# Sheet1.net
KiCad netlist of a schematic drawn in Altium Designer
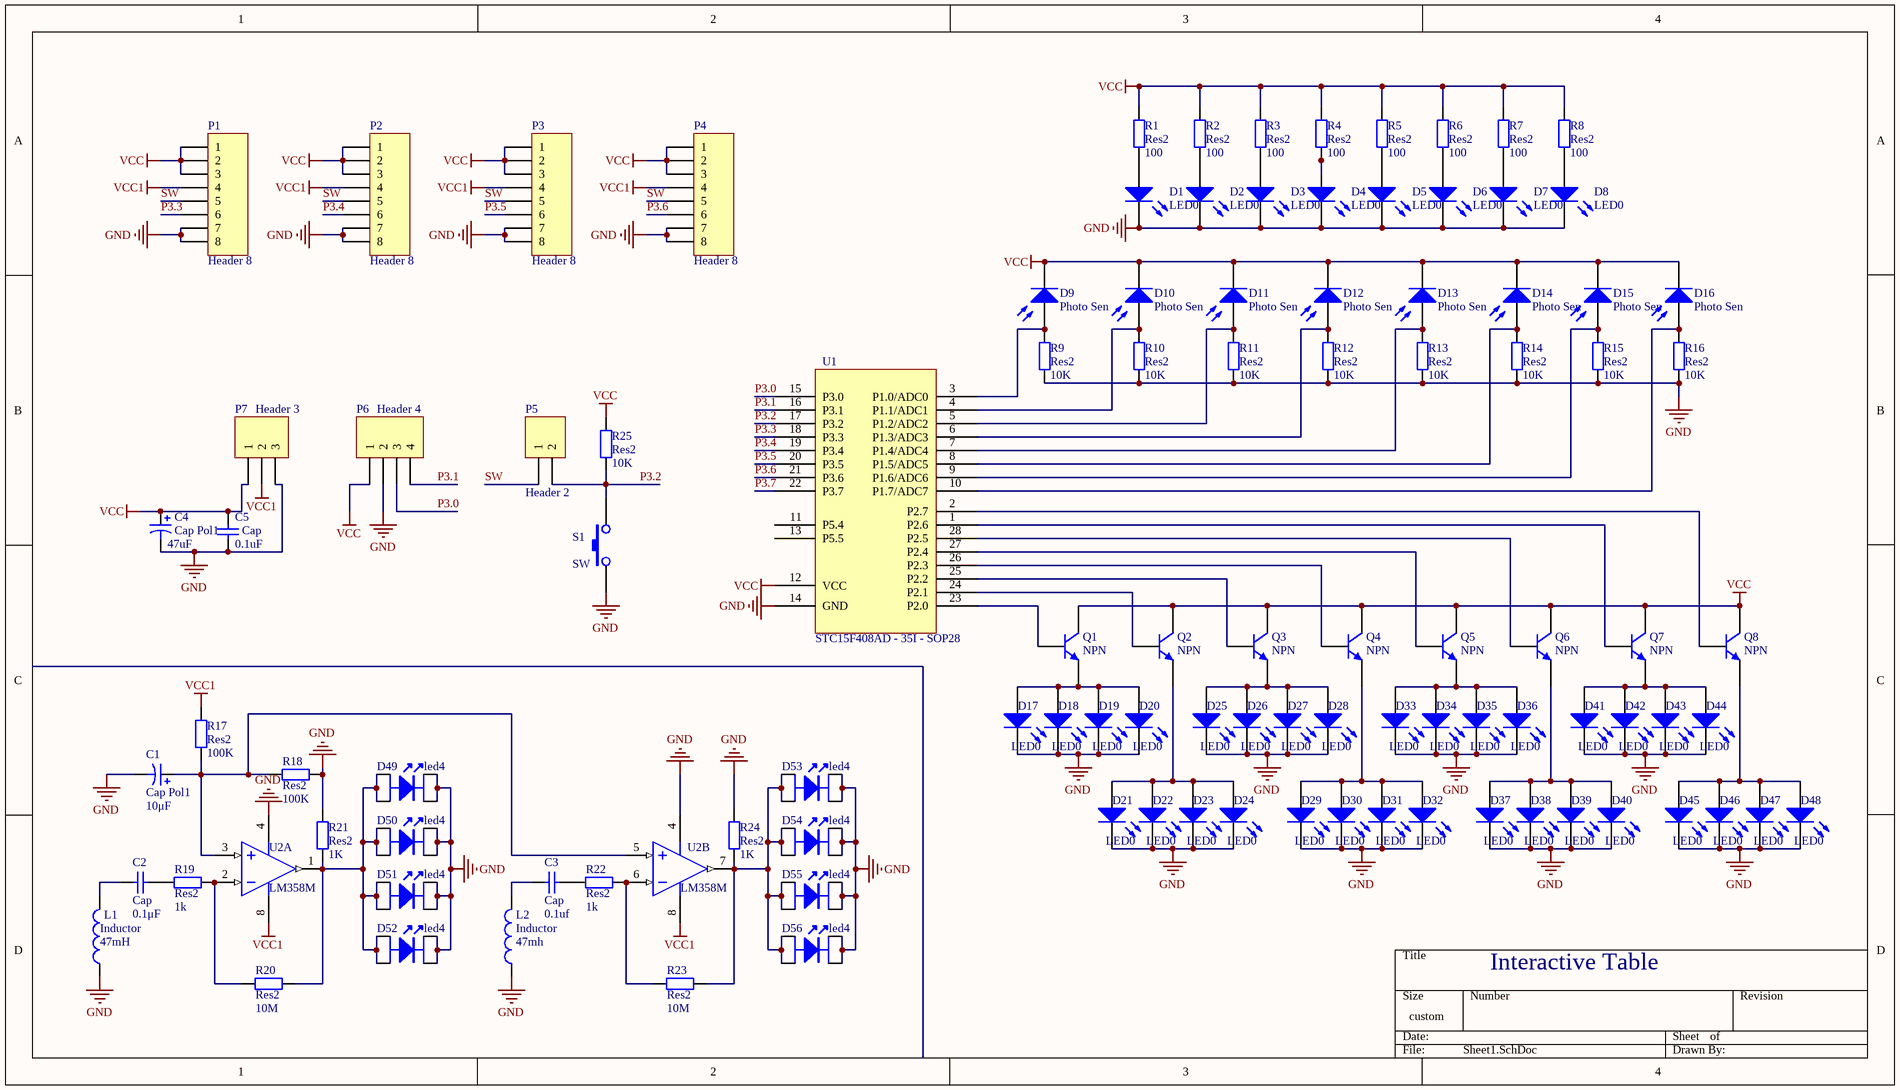
[diagram p0: Sheet1.SchDoc]

(export (version "E")
  (design (tool "Eeschema 10.0.6"))
  (components
    (comp (ref "C1")
      (value "Cap Pol1")
      (footprint "IECP10 W")
      (description "Polarized Capacitor (Radial)")
      (fields (field (name "ALTIUM_VALUE") "10μF") (field (name "PUBLISHER") "Altium Limited"))
      (libsource (lib "Miscellaneous Devices") (part "Cap Pol1"))
    )
    (comp (ref "C2")
      (value "Cap")
      (footprint "iCap")
      (description "Capacitor")
      (fields (field (name "ALTIUM_VALUE") "0.1μF") (field (name "PUBLISHER") "Altium Limited"))
      (libsource (lib "Miscellaneous Devices") (part "Cap"))
    )
    (comp (ref "C3")
      (value "Cap")
      (footprint "iCap")
      (description "Capacitor")
      (fields (field (name "ALTIUM_VALUE") "0.1uf") (field (name "PUBLISHER") "Altium Limited"))
      (libsource (lib "Miscellaneous Devices") (part "Cap"))
    )
    (comp (ref "C4")
      (value "Cap Pol1")
      (footprint "IECP10 W")
      (description "Polarized Capacitor (Radial)")
      (fields (field (name "ALTIUM_VALUE") "47uF") (field (name "PUBLISHER") "Altium Limited"))
      (libsource (lib "Miscellaneous Devices") (part "Cap Pol1"))
    )
    (comp (ref "C5")
      (value "Cap")
      (footprint "iCap")
      (description "Capacitor")
      (fields (field (name "ALTIUM_VALUE") "0.1uF") (field (name "PUBLISHER") "Altium Limited"))
      (libsource (lib "Miscellaneous Devices") (part "Cap"))
    )
    (comp (ref "D1")
      (value "LED0")
      (footprint "iLED_IR")
      (description "Typical INFRARED GaAs LED")
      (fields (field (name "PUBLISHER") "Altium Limited"))
      (libsource (lib "Miscellaneous Devices") (part "LED0"))
    )
    (comp (ref "D2")
      (value "LED0")
      (footprint "iLED_IR")
      (description "Typical INFRARED GaAs LED")
      (fields (field (name "PUBLISHER") "Altium Limited"))
      (libsource (lib "Miscellaneous Devices") (part "LED0"))
    )
    (comp (ref "D3")
      (value "LED0")
      (footprint "iLED_IR")
      (description "Typical INFRARED GaAs LED")
      (fields (field (name "PUBLISHER") "Altium Limited"))
      (libsource (lib "Miscellaneous Devices") (part "LED0"))
    )
    (comp (ref "D4")
      (value "LED0")
      (footprint "iLED_IR")
      (description "Typical INFRARED GaAs LED")
      (fields (field (name "PUBLISHER") "Altium Limited"))
      (libsource (lib "Miscellaneous Devices") (part "LED0"))
    )
    (comp (ref "D5")
      (value "LED0")
      (footprint "iLED_IR")
      (description "Typical INFRARED GaAs LED")
      (fields (field (name "PUBLISHER") "Altium Limited"))
      (libsource (lib "Miscellaneous Devices") (part "LED0"))
    )
    (comp (ref "D6")
      (value "LED0")
      (footprint "iLED_IR")
      (description "Typical INFRARED GaAs LED")
      (fields (field (name "PUBLISHER") "Altium Limited"))
      (libsource (lib "Miscellaneous Devices") (part "LED0"))
    )
    (comp (ref "D7")
      (value "LED0")
      (footprint "iLED_IR")
      (description "Typical INFRARED GaAs LED")
      (fields (field (name "PUBLISHER") "Altium Limited"))
      (libsource (lib "Miscellaneous Devices") (part "LED0"))
    )
    (comp (ref "D8")
      (value "LED0")
      (footprint "iLED_IR")
      (description "Typical INFRARED GaAs LED")
      (fields (field (name "PUBLISHER") "Altium Limited"))
      (libsource (lib "Miscellaneous Devices") (part "LED0"))
    )
    (comp (ref "D9")
      (value "Photo Sen")
      (footprint "iLED_PS")
      (description "Photosensitive Diode")
      (fields (field (name "PUBLISHER") "Altium Limited"))
      (libsource (lib "Miscellaneous Devices") (part "Photo Sen"))
    )
    (comp (ref "D10")
      (value "Photo Sen")
      (footprint "iLED_PS")
      (description "Photosensitive Diode")
      (fields (field (name "PUBLISHER") "Altium Limited"))
      (libsource (lib "Miscellaneous Devices") (part "Photo Sen"))
    )
    (comp (ref "D11")
      (value "Photo Sen")
      (footprint "iLED_PS")
      (description "Photosensitive Diode")
      (fields (field (name "PUBLISHER") "Altium Limited"))
      (libsource (lib "Miscellaneous Devices") (part "Photo Sen"))
    )
    (comp (ref "D12")
      (value "Photo Sen")
      (footprint "iLED_PS")
      (description "Photosensitive Diode")
      (fields (field (name "PUBLISHER") "Altium Limited"))
      (libsource (lib "Miscellaneous Devices") (part "Photo Sen"))
    )
    (comp (ref "D13")
      (value "Photo Sen")
      (footprint "iLED_PS")
      (description "Photosensitive Diode")
      (fields (field (name "PUBLISHER") "Altium Limited"))
      (libsource (lib "Miscellaneous Devices") (part "Photo Sen"))
    )
    (comp (ref "D14")
      (value "Photo Sen")
      (footprint "iLED_PS")
      (description "Photosensitive Diode")
      (fields (field (name "PUBLISHER") "Altium Limited"))
      (libsource (lib "Miscellaneous Devices") (part "Photo Sen"))
    )
    (comp (ref "D15")
      (value "Photo Sen")
      (footprint "iLED_PS")
      (description "Photosensitive Diode")
      (fields (field (name "PUBLISHER") "Altium Limited"))
      (libsource (lib "Miscellaneous Devices") (part "Photo Sen"))
    )
    (comp (ref "D16")
      (value "Photo Sen")
      (footprint "iLED_PS")
      (description "Photosensitive Diode")
      (fields (field (name "PUBLISHER") "Altium Limited"))
      (libsource (lib "Miscellaneous Devices") (part "Photo Sen"))
    )
    (comp (ref "D17")
      (value "LED0")
      (footprint "iLED")
      (description "Typical INFRARED GaAs LED")
      (fields (field (name "PUBLISHER") "Altium Limited"))
      (libsource (lib "Miscellaneous Devices") (part "LED0"))
    )
    (comp (ref "D18")
      (value "LED0")
      (footprint "iLED")
      (description "Typical INFRARED GaAs LED")
      (fields (field (name "PUBLISHER") "Altium Limited"))
      (libsource (lib "Miscellaneous Devices") (part "LED0"))
    )
    (comp (ref "D19")
      (value "LED0")
      (footprint "iLED")
      (description "Typical INFRARED GaAs LED")
      (fields (field (name "PUBLISHER") "Altium Limited"))
      (libsource (lib "Miscellaneous Devices") (part "LED0"))
    )
    (comp (ref "D20")
      (value "LED0")
      (footprint "iLED")
      (description "Typical INFRARED GaAs LED")
      (fields (field (name "PUBLISHER") "Altium Limited"))
      (libsource (lib "Miscellaneous Devices") (part "LED0"))
    )
    (comp (ref "D21")
      (value "LED0")
      (footprint "iLED")
      (description "Typical INFRARED GaAs LED")
      (fields (field (name "PUBLISHER") "Altium Limited"))
      (libsource (lib "Miscellaneous Devices") (part "LED0"))
    )
    (comp (ref "D22")
      (value "LED0")
      (footprint "iLED")
      (description "Typical INFRARED GaAs LED")
      (fields (field (name "PUBLISHER") "Altium Limited"))
      (libsource (lib "Miscellaneous Devices") (part "LED0"))
    )
    (comp (ref "D23")
      (value "LED0")
      (footprint "iLED")
      (description "Typical INFRARED GaAs LED")
      (fields (field (name "PUBLISHER") "Altium Limited"))
      (libsource (lib "Miscellaneous Devices") (part "LED0"))
    )
    (comp (ref "D24")
      (value "LED0")
      (footprint "iLED")
      (description "Typical INFRARED GaAs LED")
      (fields (field (name "PUBLISHER") "Altium Limited"))
      (libsource (lib "Miscellaneous Devices") (part "LED0"))
    )
    (comp (ref "D25")
      (value "LED0")
      (footprint "iLED")
      (description "Typical INFRARED GaAs LED")
      (fields (field (name "PUBLISHER") "Altium Limited"))
      (libsource (lib "Miscellaneous Devices") (part "LED0"))
    )
    (comp (ref "D26")
      (value "LED0")
      (footprint "iLED")
      (description "Typical INFRARED GaAs LED")
      (fields (field (name "PUBLISHER") "Altium Limited"))
      (libsource (lib "Miscellaneous Devices") (part "LED0"))
    )
    (comp (ref "D27")
      (value "LED0")
      (footprint "iLED")
      (description "Typical INFRARED GaAs LED")
      (fields (field (name "PUBLISHER") "Altium Limited"))
      (libsource (lib "Miscellaneous Devices") (part "LED0"))
    )
    (comp (ref "D28")
      (value "LED0")
      (footprint "iLED")
      (description "Typical INFRARED GaAs LED")
      (fields (field (name "PUBLISHER") "Altium Limited"))
      (libsource (lib "Miscellaneous Devices") (part "LED0"))
    )
    (comp (ref "D29")
      (value "LED0")
      (footprint "iLED")
      (description "Typical INFRARED GaAs LED")
      (fields (field (name "PUBLISHER") "Altium Limited"))
      (libsource (lib "Miscellaneous Devices") (part "LED0"))
    )
    (comp (ref "D30")
      (value "LED0")
      (footprint "iLED")
      (description "Typical INFRARED GaAs LED")
      (fields (field (name "PUBLISHER") "Altium Limited"))
      (libsource (lib "Miscellaneous Devices") (part "LED0"))
    )
    (comp (ref "D31")
      (value "LED0")
      (footprint "iLED")
      (description "Typical INFRARED GaAs LED")
      (fields (field (name "PUBLISHER") "Altium Limited"))
      (libsource (lib "Miscellaneous Devices") (part "LED0"))
    )
    (comp (ref "D32")
      (value "LED0")
      (footprint "iLED")
      (description "Typical INFRARED GaAs LED")
      (fields (field (name "PUBLISHER") "Altium Limited"))
      (libsource (lib "Miscellaneous Devices") (part "LED0"))
    )
    (comp (ref "D33")
      (value "LED0")
      (footprint "iLED")
      (description "Typical INFRARED GaAs LED")
      (fields (field (name "PUBLISHER") "Altium Limited"))
      (libsource (lib "Miscellaneous Devices") (part "LED0"))
    )
    (comp (ref "D34")
      (value "LED0")
      (footprint "iLED")
      (description "Typical INFRARED GaAs LED")
      (fields (field (name "PUBLISHER") "Altium Limited"))
      (libsource (lib "Miscellaneous Devices") (part "LED0"))
    )
    (comp (ref "D35")
      (value "LED0")
      (footprint "iLED")
      (description "Typical INFRARED GaAs LED")
      (fields (field (name "PUBLISHER") "Altium Limited"))
      (libsource (lib "Miscellaneous Devices") (part "LED0"))
    )
    (comp (ref "D36")
      (value "LED0")
      (footprint "iLED")
      (description "Typical INFRARED GaAs LED")
      (fields (field (name "PUBLISHER") "Altium Limited"))
      (libsource (lib "Miscellaneous Devices") (part "LED0"))
    )
    (comp (ref "D37")
      (value "LED0")
      (footprint "iLED")
      (description "Typical INFRARED GaAs LED")
      (fields (field (name "PUBLISHER") "Altium Limited"))
      (libsource (lib "Miscellaneous Devices") (part "LED0"))
    )
    (comp (ref "D38")
      (value "LED0")
      (footprint "iLED")
      (description "Typical INFRARED GaAs LED")
      (fields (field (name "PUBLISHER") "Altium Limited"))
      (libsource (lib "Miscellaneous Devices") (part "LED0"))
    )
    (comp (ref "D39")
      (value "LED0")
      (footprint "iLED")
      (description "Typical INFRARED GaAs LED")
      (fields (field (name "PUBLISHER") "Altium Limited"))
      (libsource (lib "Miscellaneous Devices") (part "LED0"))
    )
    (comp (ref "D40")
      (value "LED0")
      (footprint "iLED")
      (description "Typical INFRARED GaAs LED")
      (fields (field (name "PUBLISHER") "Altium Limited"))
      (libsource (lib "Miscellaneous Devices") (part "LED0"))
    )
    (comp (ref "D41")
      (value "LED0")
      (footprint "iLED")
      (description "Typical INFRARED GaAs LED")
      (fields (field (name "PUBLISHER") "Altium Limited"))
      (libsource (lib "Miscellaneous Devices") (part "LED0"))
    )
    (comp (ref "D42")
      (value "LED0")
      (footprint "iLED")
      (description "Typical INFRARED GaAs LED")
      (fields (field (name "PUBLISHER") "Altium Limited"))
      (libsource (lib "Miscellaneous Devices") (part "LED0"))
    )
    (comp (ref "D43")
      (value "LED0")
      (footprint "iLED")
      (description "Typical INFRARED GaAs LED")
      (fields (field (name "PUBLISHER") "Altium Limited"))
      (libsource (lib "Miscellaneous Devices") (part "LED0"))
    )
    (comp (ref "D44")
      (value "LED0")
      (footprint "iLED")
      (description "Typical INFRARED GaAs LED")
      (fields (field (name "PUBLISHER") "Altium Limited"))
      (libsource (lib "Miscellaneous Devices") (part "LED0"))
    )
    (comp (ref "D45")
      (value "LED0")
      (footprint "iLED")
      (description "Typical INFRARED GaAs LED")
      (fields (field (name "PUBLISHER") "Altium Limited"))
      (libsource (lib "Miscellaneous Devices") (part "LED0"))
    )
    (comp (ref "D46")
      (value "LED0")
      (footprint "iLED")
      (description "Typical INFRARED GaAs LED")
      (fields (field (name "PUBLISHER") "Altium Limited"))
      (libsource (lib "Miscellaneous Devices") (part "LED0"))
    )
    (comp (ref "D47")
      (value "LED0")
      (footprint "iLED")
      (description "Typical INFRARED GaAs LED")
      (fields (field (name "PUBLISHER") "Altium Limited"))
      (libsource (lib "Miscellaneous Devices") (part "LED0"))
    )
    (comp (ref "D48")
      (value "LED0")
      (footprint "iLED")
      (description "Typical INFRARED GaAs LED")
      (fields (field (name "PUBLISHER") "Altium Limited"))
      (libsource (lib "Miscellaneous Devices") (part "LED0"))
    )
    (comp (ref "D49") (value "led4") (libsource (lib "Schlib1") (part "led4")))
    (comp (ref "D50") (value "led4") (libsource (lib "Schlib1") (part "led4")))
    (comp (ref "D51") (value "led4") (libsource (lib "Schlib1") (part "led4")))
    (comp (ref "D52") (value "led4") (libsource (lib "Schlib1") (part "led4")))
    (comp (ref "D53") (value "led4") (libsource (lib "Schlib1") (part "led4")))
    (comp (ref "D54") (value "led4") (libsource (lib "Schlib1") (part "led4")))
    (comp (ref "D55") (value "led4") (libsource (lib "Schlib1") (part "led4")))
    (comp (ref "D56") (value "led4") (libsource (lib "Schlib1") (part "led4")))
    (comp (ref "L1")
      (value "Inductor")
      (footprint "iL")
      (fields (field (name "ALTIUM_VALUE") "47mH") (field (name "PUBLISHER") "Altium Limited"))
      (libsource (lib "Miscellaneous Devices") (part "Inductor"))
    )
    (comp (ref "L2")
      (value "Inductor")
      (footprint "iL")
      (fields (field (name "ALTIUM_VALUE") "47mh") (field (name "PUBLISHER") "Altium Limited"))
      (libsource (lib "Miscellaneous Devices") (part "Inductor"))
    )
    (comp (ref "P1")
      (value "Header 8")
      (footprint "HDR1X8H")
      (description "Header, 8-Pin")
      (fields (field (name "PUBLISHER") "Altium Limited"))
      (libsource (lib "Miscellaneous Connectors") (part "Header 8"))
    )
    (comp (ref "P2")
      (value "Header 8")
      (footprint "HDR1X8H")
      (description "Header, 8-Pin")
      (fields (field (name "PUBLISHER") "Altium Limited"))
      (libsource (lib "Miscellaneous Connectors") (part "Header 8"))
    )
    (comp (ref "P3")
      (value "Header 8")
      (footprint "HDR1X8")
      (description "Header, 8-Pin")
      (fields (field (name "PUBLISHER") "Altium Limited"))
      (libsource (lib "Miscellaneous Connectors") (part "Header 8"))
    )
    (comp (ref "P4")
      (value "Header 8")
      (footprint "HDR1X8")
      (description "Header, 8-Pin")
      (fields (field (name "PUBLISHER") "Altium Limited"))
      (libsource (lib "Miscellaneous Connectors") (part "Header 8"))
    )
    (comp (ref "P5")
      (value "Header 2")
      (footprint "HDR1X2")
      (description "Header, 2-Pin")
      (fields (field (name "PUBLISHER") "Altium Limited"))
      (libsource (lib "Miscellaneous Connectors") (part "Header 2"))
    )
    (comp (ref "P6")
      (value "Header 4")
      (footprint "HDR1X4")
      (description "Header, 4-Pin")
      (fields (field (name "PUBLISHER") "Altium Limited"))
      (libsource (lib "Miscellaneous Connectors") (part "Header 4"))
    )
    (comp (ref "P7")
      (value "Header 3")
      (footprint "HBX3P")
      (description "Header, 3-Pin")
      (fields (field (name "PUBLISHER") "Altium Limited"))
      (libsource (lib "Miscellaneous Connectors") (part "Header 3"))
    )
    (comp (ref "Q1")
      (value "NPN")
      (footprint "NPN")
      (description "NPN Bipolar Transistor")
      (fields (field (name "PUBLISHER") "Altium Limited"))
      (libsource (lib "Miscellaneous Devices") (part "NPN"))
    )
    (comp (ref "Q2")
      (value "NPN")
      (footprint "NPN")
      (description "NPN Bipolar Transistor")
      (fields (field (name "PUBLISHER") "Altium Limited"))
      (libsource (lib "Miscellaneous Devices") (part "NPN"))
    )
    (comp (ref "Q3")
      (value "NPN")
      (footprint "NPN")
      (description "NPN Bipolar Transistor")
      (fields (field (name "PUBLISHER") "Altium Limited"))
      (libsource (lib "Miscellaneous Devices") (part "NPN"))
    )
    (comp (ref "Q4")
      (value "NPN")
      (footprint "NPN")
      (description "NPN Bipolar Transistor")
      (fields (field (name "PUBLISHER") "Altium Limited"))
      (libsource (lib "Miscellaneous Devices") (part "NPN"))
    )
    (comp (ref "Q5")
      (value "NPN")
      (footprint "NPN")
      (description "NPN Bipolar Transistor")
      (fields (field (name "PUBLISHER") "Altium Limited"))
      (libsource (lib "Miscellaneous Devices") (part "NPN"))
    )
    (comp (ref "Q6")
      (value "NPN")
      (footprint "NPN")
      (description "NPN Bipolar Transistor")
      (fields (field (name "PUBLISHER") "Altium Limited"))
      (libsource (lib "Miscellaneous Devices") (part "NPN"))
    )
    (comp (ref "Q7")
      (value "NPN")
      (footprint "NPN")
      (description "NPN Bipolar Transistor")
      (fields (field (name "PUBLISHER") "Altium Limited"))
      (libsource (lib "Miscellaneous Devices") (part "NPN"))
    )
    (comp (ref "Q8")
      (value "NPN")
      (footprint "NPN")
      (description "NPN Bipolar Transistor")
      (fields (field (name "PUBLISHER") "Altium Limited"))
      (libsource (lib "Miscellaneous Devices") (part "NPN"))
    )
    (comp (ref "R1")
      (value "Res2")
      (footprint "AXIAL-0.4")
      (description "Resistor")
      (fields (field (name "ALTIUM_VALUE") "100") (field (name "PUBLISHER") "Altium Limited"))
      (libsource (lib "") (part "Res2_1"))
    )
    (comp (ref "R2")
      (value "Res2")
      (footprint "AXIAL-0.4")
      (description "Resistor")
      (fields (field (name "ALTIUM_VALUE") "100") (field (name "PUBLISHER") "Altium Limited"))
      (libsource (lib "") (part "Res2_1"))
    )
    (comp (ref "R3")
      (value "Res2")
      (footprint "AXIAL-0.4")
      (description "Resistor")
      (fields (field (name "ALTIUM_VALUE") "100") (field (name "PUBLISHER") "Altium Limited"))
      (libsource (lib "") (part "Res2_1"))
    )
    (comp (ref "R4")
      (value "Res2")
      (footprint "AXIAL-0.4")
      (description "Resistor")
      (fields (field (name "ALTIUM_VALUE") "100") (field (name "PUBLISHER") "Altium Limited"))
      (libsource (lib "") (part "Res2_1"))
    )
    (comp (ref "R5")
      (value "Res2")
      (footprint "AXIAL-0.4")
      (description "Resistor")
      (fields (field (name "ALTIUM_VALUE") "100") (field (name "PUBLISHER") "Altium Limited"))
      (libsource (lib "") (part "Res2_1"))
    )
    (comp (ref "R6")
      (value "Res2")
      (footprint "AXIAL-0.4")
      (description "Resistor")
      (fields (field (name "ALTIUM_VALUE") "100") (field (name "PUBLISHER") "Altium Limited"))
      (libsource (lib "") (part "Res2_1"))
    )
    (comp (ref "R7")
      (value "Res2")
      (footprint "AXIAL-0.4")
      (description "Resistor")
      (fields (field (name "ALTIUM_VALUE") "100") (field (name "PUBLISHER") "Altium Limited"))
      (libsource (lib "") (part "Res2_1"))
    )
    (comp (ref "R8")
      (value "Res2")
      (footprint "AXIAL-0.4")
      (description "Resistor")
      (fields (field (name "ALTIUM_VALUE") "100") (field (name "PUBLISHER") "Altium Limited"))
      (libsource (lib "") (part "Res2_1"))
    )
    (comp (ref "R9")
      (value "Res2")
      (footprint "AXIAL-0.4")
      (description "Resistor")
      (fields (field (name "ALTIUM_VALUE") "10K") (field (name "PUBLISHER") "Altium Limited"))
      (libsource (lib "") (part "Res2_1"))
    )
    (comp (ref "R10")
      (value "Res2")
      (footprint "AXIAL-0.4")
      (description "Resistor")
      (fields (field (name "ALTIUM_VALUE") "10K") (field (name "PUBLISHER") "Altium Limited"))
      (libsource (lib "") (part "Res2_1"))
    )
    (comp (ref "R11")
      (value "Res2")
      (footprint "AXIAL-0.4")
      (description "Resistor")
      (fields (field (name "ALTIUM_VALUE") "10K") (field (name "PUBLISHER") "Altium Limited"))
      (libsource (lib "") (part "Res2_1"))
    )
    (comp (ref "R12")
      (value "Res2")
      (footprint "AXIAL-0.4")
      (description "Resistor")
      (fields (field (name "ALTIUM_VALUE") "10K") (field (name "PUBLISHER") "Altium Limited"))
      (libsource (lib "") (part "Res2_1"))
    )
    (comp (ref "R13")
      (value "Res2")
      (footprint "AXIAL-0.4")
      (description "Resistor")
      (fields (field (name "ALTIUM_VALUE") "10K") (field (name "PUBLISHER") "Altium Limited"))
      (libsource (lib "") (part "Res2_1"))
    )
    (comp (ref "R14")
      (value "Res2")
      (footprint "AXIAL-0.4")
      (description "Resistor")
      (fields (field (name "ALTIUM_VALUE") "10K") (field (name "PUBLISHER") "Altium Limited"))
      (libsource (lib "") (part "Res2_1"))
    )
    (comp (ref "R15")
      (value "Res2")
      (footprint "AXIAL-0.4")
      (description "Resistor")
      (fields (field (name "ALTIUM_VALUE") "10K") (field (name "PUBLISHER") "Altium Limited"))
      (libsource (lib "") (part "Res2_1"))
    )
    (comp (ref "R16")
      (value "Res2")
      (footprint "AXIAL-0.4")
      (description "Resistor")
      (fields (field (name "ALTIUM_VALUE") "10K") (field (name "PUBLISHER") "Altium Limited"))
      (libsource (lib "") (part "Res2_1"))
    )
    (comp (ref "R17")
      (value "Res2")
      (footprint "AXIAL-0.4")
      (description "Resistor")
      (fields (field (name "ALTIUM_VALUE") "100K") (field (name "PUBLISHER") "Altium Limited"))
      (libsource (lib "") (part "Res2_1"))
    )
    (comp (ref "R18")
      (value "Res2")
      (footprint "AXIAL-0.4")
      (description "Resistor")
      (fields (field (name "ALTIUM_VALUE") "100K") (field (name "PUBLISHER") "Altium Limited"))
      (libsource (lib "") (part "Res2_2"))
    )
    (comp (ref "R19")
      (value "Res2")
      (footprint "AXIAL-0.4")
      (description "Resistor")
      (fields (field (name "ALTIUM_VALUE") "1k") (field (name "PUBLISHER") "Altium Limited"))
      (libsource (lib "Miscellaneous Devices") (part "Res2"))
    )
    (comp (ref "R20")
      (value "Res2")
      (footprint "AXIAL-0.4")
      (description "Resistor")
      (fields (field (name "ALTIUM_VALUE") "10M") (field (name "PUBLISHER") "Altium Limited"))
      (libsource (lib "Miscellaneous Devices") (part "Res2"))
    )
    (comp (ref "R21")
      (value "Res2")
      (footprint "AXIAL-0.4")
      (description "Resistor")
      (fields (field (name "ALTIUM_VALUE") "1K") (field (name "PUBLISHER") "Altium Limited"))
      (libsource (lib "") (part "Res2_3"))
    )
    (comp (ref "R22")
      (value "Res2")
      (footprint "AXIAL-0.4")
      (description "Resistor")
      (fields (field (name "ALTIUM_VALUE") "1k") (field (name "PUBLISHER") "Altium Limited"))
      (libsource (lib "") (part "Res2_2"))
    )
    (comp (ref "R23")
      (value "Res2")
      (footprint "AXIAL-0.4")
      (description "Resistor")
      (fields (field (name "ALTIUM_VALUE") "10M") (field (name "PUBLISHER") "Altium Limited"))
      (libsource (lib "") (part "Res2_2"))
    )
    (comp (ref "R24")
      (value "Res2")
      (footprint "AXIAL-0.4")
      (description "Resistor")
      (fields (field (name "ALTIUM_VALUE") "1K") (field (name "PUBLISHER") "Altium Limited"))
      (libsource (lib "") (part "Res2_1"))
    )
    (comp (ref "R25")
      (value "Res2")
      (footprint "AXIAL-0.4")
      (description "Resistor")
      (fields (field (name "ALTIUM_VALUE") "10K") (field (name "PUBLISHER") "Altium Limited"))
      (libsource (lib "") (part "Res2_1"))
    )
    (comp (ref "S1") (value "SW") (footprint "SW") (libsource (lib "开关") (part "微动开关")))
    (comp (ref "U1")
      (value "STC15F408AD - 35I - SOP28")
      (footprint "SOP28")
      (libsource (lib "STC_sch") (part "STC15F408AD - 35I - SOP28"))
    )
    (comp (ref "U2")
      (value "LM358M")
      (footprint "M08A_N")
      (description "Low Power Dual Operational Amplifier")
      (fields
        (field (name "MANUFACTURER") "National Semiconductor")
        (field (name "DIGIKEYPARTNUMBER") "LM358MXCT-ND")
        (field (name "PUBLISHER") "Altium Limited")
      )
      (libsource (lib "NSC Amplifier") (part "LM358M"))
    )
  )
  (nets
    (net (code "1") (name "/P3.0") (class "Default")
      (node (ref "P6") (pin "3") (pinfunction "3_3") (pintype "passive"))
      (node (ref "U1") (pin "15") (pinfunction "P3.0_15") (pintype "passive"))
    )
    (net (code "2") (name "/P3.1") (class "Default")
      (node (ref "P6") (pin "4") (pinfunction "4_4") (pintype "passive"))
      (node (ref "U1") (pin "16") (pinfunction "P3.1_16") (pintype "passive"))
    )
    (net (code "3") (name "/P3.2") (class "Default")
      (node (ref "P5") (pin "2") (pinfunction "2_2") (pintype "passive"))
      (node (ref "R25") (pin "1") (pinfunction "1_1") (pintype "passive"))
      (node (ref "S1") (pin "2") (pinfunction "2_2") (pintype "passive"))
      (node (ref "U1") (pin "17") (pinfunction "P3.2_17") (pintype "passive"))
    )
    (net (code "4") (name "/P3.3") (class "Default")
      (node (ref "P1") (pin "6") (pinfunction "6_6") (pintype "passive"))
      (node (ref "U1") (pin "18") (pinfunction "P3.3_18") (pintype "passive"))
    )
    (net (code "5") (name "/P3.4") (class "Default")
      (node (ref "P2") (pin "6") (pinfunction "6_6") (pintype "passive"))
      (node (ref "U1") (pin "19") (pinfunction "P3.4_19") (pintype "passive"))
    )
    (net (code "6") (name "/P3.5") (class "Default")
      (node (ref "P3") (pin "6") (pinfunction "6_6") (pintype "passive"))
      (node (ref "U1") (pin "20") (pinfunction "P3.5_20") (pintype "passive"))
    )
    (net (code "7") (name "/P3.6") (class "Default")
      (node (ref "P4") (pin "6") (pinfunction "6_6") (pintype "passive"))
      (node (ref "U1") (pin "21") (pinfunction "P3.6_21") (pintype "passive"))
    )
    (net (code "8") (name "/P3.7") (class "Default")
      (node (ref "U1") (pin "22") (pinfunction "P3.7_22") (pintype "passive"))
    )
    (net (code "9") (name "/SW") (class "Default")
      (node (ref "P1") (pin "5") (pinfunction "5_5") (pintype "passive"))
      (node (ref "P2") (pin "5") (pinfunction "5_5") (pintype "passive"))
      (node (ref "P3") (pin "5") (pinfunction "5_5") (pintype "passive"))
      (node (ref "P4") (pin "5") (pinfunction "5_5") (pintype "passive"))
      (node (ref "P5") (pin "1") (pinfunction "1_1") (pintype "passive"))
    )
    (net (code "10") (name "GND") (class "Default")
      (node (ref "C1") (pin "2") (pinfunction "2_2") (pintype "passive"))
      (node (ref "C4") (pin "2") (pinfunction "2_2") (pintype "passive"))
      (node (ref "C5") (pin "1") (pinfunction "1_1") (pintype "passive"))
      (node (ref "D1") (pin "2") (pinfunction "K_2") (pintype "passive"))
      (node (ref "D17") (pin "2") (pinfunction "K_2") (pintype "passive"))
      (node (ref "D18") (pin "2") (pinfunction "K_2") (pintype "passive"))
      (node (ref "D19") (pin "2") (pinfunction "K_2") (pintype "passive"))
      (node (ref "D2") (pin "2") (pinfunction "K_2") (pintype "passive"))
      (node (ref "D20") (pin "2") (pinfunction "K_2") (pintype "passive"))
      (node (ref "D21") (pin "2") (pinfunction "K_2") (pintype "passive"))
      (node (ref "D22") (pin "2") (pinfunction "K_2") (pintype "passive"))
      (node (ref "D23") (pin "2") (pinfunction "K_2") (pintype "passive"))
      (node (ref "D24") (pin "2") (pinfunction "K_2") (pintype "passive"))
      (node (ref "D25") (pin "2") (pinfunction "K_2") (pintype "passive"))
      (node (ref "D26") (pin "2") (pinfunction "K_2") (pintype "passive"))
      (node (ref "D27") (pin "2") (pinfunction "K_2") (pintype "passive"))
      (node (ref "D28") (pin "2") (pinfunction "K_2") (pintype "passive"))
      (node (ref "D29") (pin "2") (pinfunction "K_2") (pintype "passive"))
      (node (ref "D3") (pin "2") (pinfunction "K_2") (pintype "passive"))
      (node (ref "D30") (pin "2") (pinfunction "K_2") (pintype "passive"))
      (node (ref "D31") (pin "2") (pinfunction "K_2") (pintype "passive"))
      (node (ref "D32") (pin "2") (pinfunction "K_2") (pintype "passive"))
      (node (ref "D33") (pin "2") (pinfunction "K_2") (pintype "passive"))
      (node (ref "D34") (pin "2") (pinfunction "K_2") (pintype "passive"))
      (node (ref "D35") (pin "2") (pinfunction "K_2") (pintype "passive"))
      (node (ref "D36") (pin "2") (pinfunction "K_2") (pintype "passive"))
      (node (ref "D37") (pin "2") (pinfunction "K_2") (pintype "passive"))
      (node (ref "D38") (pin "2") (pinfunction "K_2") (pintype "passive"))
      (node (ref "D39") (pin "2") (pinfunction "K_2") (pintype "passive"))
      (node (ref "D4") (pin "2") (pinfunction "K_2") (pintype "passive"))
      (node (ref "D40") (pin "2") (pinfunction "K_2") (pintype "passive"))
      (node (ref "D41") (pin "2") (pinfunction "K_2") (pintype "passive"))
      (node (ref "D42") (pin "2") (pinfunction "K_2") (pintype "passive"))
      (node (ref "D43") (pin "2") (pinfunction "K_2") (pintype "passive"))
      (node (ref "D44") (pin "2") (pinfunction "K_2") (pintype "passive"))
      (node (ref "D45") (pin "2") (pinfunction "K_2") (pintype "passive"))
      (node (ref "D46") (pin "2") (pinfunction "K_2") (pintype "passive"))
      (node (ref "D47") (pin "2") (pinfunction "K_2") (pintype "passive"))
      (node (ref "D48") (pin "2") (pinfunction "K_2") (pintype "passive"))
      (node (ref "D49") (pin "3") (pinfunction "3_3") (pintype "passive"))
      (node (ref "D49") (pin "4") (pinfunction "4_4") (pintype "passive"))
      (node (ref "D5") (pin "2") (pinfunction "K_2") (pintype "passive"))
      (node (ref "D50") (pin "3") (pinfunction "3_3") (pintype "passive"))
      (node (ref "D50") (pin "4") (pinfunction "4_4") (pintype "passive"))
      (node (ref "D51") (pin "3") (pinfunction "3_3") (pintype "passive"))
      (node (ref "D51") (pin "4") (pinfunction "4_4") (pintype "passive"))
      (node (ref "D52") (pin "3") (pinfunction "3_3") (pintype "passive"))
      (node (ref "D52") (pin "4") (pinfunction "4_4") (pintype "passive"))
      (node (ref "D53") (pin "3") (pinfunction "3_3") (pintype "passive"))
      (node (ref "D53") (pin "4") (pinfunction "4_4") (pintype "passive"))
      (node (ref "D54") (pin "3") (pinfunction "3_3") (pintype "passive"))
      (node (ref "D54") (pin "4") (pinfunction "4_4") (pintype "passive"))
      (node (ref "D55") (pin "3") (pinfunction "3_3") (pintype "passive"))
      (node (ref "D55") (pin "4") (pinfunction "4_4") (pintype "passive"))
      (node (ref "D56") (pin "3") (pinfunction "3_3") (pintype "passive"))
      (node (ref "D56") (pin "4") (pinfunction "4_4") (pintype "passive"))
      (node (ref "D6") (pin "2") (pinfunction "K_2") (pintype "passive"))
      (node (ref "D7") (pin "2") (pinfunction "K_2") (pintype "passive"))
      (node (ref "D8") (pin "2") (pinfunction "K_2") (pintype "passive"))
      (node (ref "L1") (pin "1") (pinfunction "1_1") (pintype "passive"))
      (node (ref "L2") (pin "1") (pinfunction "1_1") (pintype "passive"))
      (node (ref "P1") (pin "7") (pinfunction "7_7") (pintype "passive"))
      (node (ref "P1") (pin "8") (pinfunction "8_8") (pintype "passive"))
      (node (ref "P2") (pin "7") (pinfunction "7_7") (pintype "passive"))
      (node (ref "P2") (pin "8") (pinfunction "8_8") (pintype "passive"))
      (node (ref "P3") (pin "7") (pinfunction "7_7") (pintype "passive"))
      (node (ref "P3") (pin "8") (pinfunction "8_8") (pintype "passive"))
      (node (ref "P4") (pin "7") (pinfunction "7_7") (pintype "passive"))
      (node (ref "P4") (pin "8") (pinfunction "8_8") (pintype "passive"))
      (node (ref "P6") (pin "2") (pinfunction "2_2") (pintype "passive"))
      (node (ref "P7") (pin "3") (pinfunction "3_3") (pintype "passive"))
      (node (ref "R10") (pin "1") (pinfunction "1_1") (pintype "passive"))
      (node (ref "R11") (pin "1") (pinfunction "1_1") (pintype "passive"))
      (node (ref "R12") (pin "1") (pinfunction "1_1") (pintype "passive"))
      (node (ref "R13") (pin "1") (pinfunction "1_1") (pintype "passive"))
      (node (ref "R14") (pin "1") (pinfunction "1_1") (pintype "passive"))
      (node (ref "R15") (pin "1") (pinfunction "1_1") (pintype "passive"))
      (node (ref "R16") (pin "1") (pinfunction "1_1") (pintype "passive"))
      (node (ref "R18") (pin "2") (pinfunction "2_2") (pintype "passive"))
      (node (ref "R21") (pin "1") (pinfunction "1_1") (pintype "passive"))
      (node (ref "R24") (pin "2") (pinfunction "2_2") (pintype "passive"))
      (node (ref "R9") (pin "1") (pinfunction "1_1") (pintype "passive"))
      (node (ref "S1") (pin "1") (pinfunction "1_1") (pintype "passive"))
      (node (ref "U1") (pin "14") (pinfunction "GND_14") (pintype "passive"))
      (node (ref "U2") (pin "4") (pinfunction "GND_4") (pintype "power_in"))
    )
    (net (code "11") (name "Net-(C2-Pad1)") (class "Default")
      (node (ref "C2") (pin "1") (pinfunction "1_1") (pintype "passive"))
      (node (ref "L1") (pin "2") (pinfunction "2_2") (pintype "passive"))
    )
    (net (code "12") (name "Net-(C2-Pad2)") (class "Default")
      (node (ref "C2") (pin "2") (pinfunction "2_2") (pintype "passive"))
      (node (ref "R19") (pin "2") (pinfunction "2_2") (pintype "passive"))
    )
    (net (code "13") (name "Net-(C3-Pad1)") (class "Default")
      (node (ref "C3") (pin "1") (pinfunction "1_1") (pintype "passive"))
      (node (ref "L2") (pin "2") (pinfunction "2_2") (pintype "passive"))
    )
    (net (code "14") (name "Net-(C3-Pad2)") (class "Default")
      (node (ref "C3") (pin "2") (pinfunction "2_2") (pintype "passive"))
      (node (ref "R22") (pin "1") (pinfunction "1_1") (pintype "passive"))
    )
    (net (code "15") (name "Net-(D1-A)") (class "Default")
      (node (ref "D1") (pin "1") (pinfunction "A_1") (pintype "passive"))
      (node (ref "R1") (pin "1") (pinfunction "1_1") (pintype "passive"))
    )
    (net (code "16") (name "Net-(D2-A)") (class "Default")
      (node (ref "D2") (pin "1") (pinfunction "A_1") (pintype "passive"))
      (node (ref "R2") (pin "1") (pinfunction "1_1") (pintype "passive"))
    )
    (net (code "17") (name "Net-(D3-A)") (class "Default")
      (node (ref "D3") (pin "1") (pinfunction "A_1") (pintype "passive"))
      (node (ref "R3") (pin "1") (pinfunction "1_1") (pintype "passive"))
    )
    (net (code "18") (name "Net-(D4-A)") (class "Default")
      (node (ref "D4") (pin "1") (pinfunction "A_1") (pintype "passive"))
      (node (ref "R4") (pin "1") (pinfunction "1_1") (pintype "passive"))
    )
    (net (code "19") (name "Net-(D5-A)") (class "Default")
      (node (ref "D5") (pin "1") (pinfunction "A_1") (pintype "passive"))
      (node (ref "R5") (pin "1") (pinfunction "1_1") (pintype "passive"))
    )
    (net (code "20") (name "Net-(D6-A)") (class "Default")
      (node (ref "D6") (pin "1") (pinfunction "A_1") (pintype "passive"))
      (node (ref "R6") (pin "1") (pinfunction "1_1") (pintype "passive"))
    )
    (net (code "21") (name "Net-(D7-A)") (class "Default")
      (node (ref "D7") (pin "1") (pinfunction "A_1") (pintype "passive"))
      (node (ref "R7") (pin "1") (pinfunction "1_1") (pintype "passive"))
    )
    (net (code "22") (name "Net-(D8-A)") (class "Default")
      (node (ref "D8") (pin "1") (pinfunction "A_1") (pintype "passive"))
      (node (ref "R8") (pin "1") (pinfunction "1_1") (pintype "passive"))
    )
    (net (code "23") (name "Net-(D9-A)") (class "Default")
      (node (ref "D9") (pin "1") (pinfunction "A_1") (pintype "passive"))
      (node (ref "R9") (pin "2") (pinfunction "2_2") (pintype "passive"))
      (node (ref "U1") (pin "3") (pinfunction "P1.0/ADC0_3") (pintype "passive"))
    )
    (net (code "24") (name "Net-(D10-A)") (class "Default")
      (node (ref "D10") (pin "1") (pinfunction "A_1") (pintype "passive"))
      (node (ref "R10") (pin "2") (pinfunction "2_2") (pintype "passive"))
      (node (ref "U1") (pin "4") (pinfunction "P1.1/ADC1_4") (pintype "passive"))
    )
    (net (code "25") (name "Net-(D11-A)") (class "Default")
      (node (ref "D11") (pin "1") (pinfunction "A_1") (pintype "passive"))
      (node (ref "R11") (pin "2") (pinfunction "2_2") (pintype "passive"))
      (node (ref "U1") (pin "5") (pinfunction "P1.2/ADC2_5") (pintype "passive"))
    )
    (net (code "26") (name "Net-(D12-A)") (class "Default")
      (node (ref "D12") (pin "1") (pinfunction "A_1") (pintype "passive"))
      (node (ref "R12") (pin "2") (pinfunction "2_2") (pintype "passive"))
      (node (ref "U1") (pin "6") (pinfunction "P1.3/ADC3_6") (pintype "passive"))
    )
    (net (code "27") (name "Net-(D13-A)") (class "Default")
      (node (ref "D13") (pin "1") (pinfunction "A_1") (pintype "passive"))
      (node (ref "R13") (pin "2") (pinfunction "2_2") (pintype "passive"))
      (node (ref "U1") (pin "7") (pinfunction "P1.4/ADC4_7") (pintype "passive"))
    )
    (net (code "28") (name "Net-(D14-A)") (class "Default")
      (node (ref "D14") (pin "1") (pinfunction "A_1") (pintype "passive"))
      (node (ref "R14") (pin "2") (pinfunction "2_2") (pintype "passive"))
      (node (ref "U1") (pin "8") (pinfunction "P1.5/ADC5_8") (pintype "passive"))
    )
    (net (code "29") (name "Net-(D15-A)") (class "Default")
      (node (ref "D15") (pin "1") (pinfunction "A_1") (pintype "passive"))
      (node (ref "R15") (pin "2") (pinfunction "2_2") (pintype "passive"))
      (node (ref "U1") (pin "9") (pinfunction "P1.6/ADC6_9") (pintype "passive"))
    )
    (net (code "30") (name "Net-(D16-A)") (class "Default")
      (node (ref "D16") (pin "1") (pinfunction "A_1") (pintype "passive"))
      (node (ref "R16") (pin "2") (pinfunction "2_2") (pintype "passive"))
      (node (ref "U1") (pin "10") (pinfunction "P1.7/ADC7_10") (pintype "passive"))
    )
    (net (code "31") (name "Net-(D17-A)") (class "Default")
      (node (ref "D17") (pin "1") (pinfunction "A_1") (pintype "passive"))
      (node (ref "D18") (pin "1") (pinfunction "A_1") (pintype "passive"))
      (node (ref "D19") (pin "1") (pinfunction "A_1") (pintype "passive"))
      (node (ref "D20") (pin "1") (pinfunction "A_1") (pintype "passive"))
      (node (ref "Q1") (pin "3") (pinfunction "E_3") (pintype "passive"))
    )
    (net (code "32") (name "Net-(D21-A)") (class "Default")
      (node (ref "D21") (pin "1") (pinfunction "A_1") (pintype "passive"))
      (node (ref "D22") (pin "1") (pinfunction "A_1") (pintype "passive"))
      (node (ref "D23") (pin "1") (pinfunction "A_1") (pintype "passive"))
      (node (ref "D24") (pin "1") (pinfunction "A_1") (pintype "passive"))
      (node (ref "Q2") (pin "3") (pinfunction "E_3") (pintype "passive"))
    )
    (net (code "33") (name "Net-(D25-A)") (class "Default")
      (node (ref "D25") (pin "1") (pinfunction "A_1") (pintype "passive"))
      (node (ref "D26") (pin "1") (pinfunction "A_1") (pintype "passive"))
      (node (ref "D27") (pin "1") (pinfunction "A_1") (pintype "passive"))
      (node (ref "D28") (pin "1") (pinfunction "A_1") (pintype "passive"))
      (node (ref "Q3") (pin "3") (pinfunction "E_3") (pintype "passive"))
    )
    (net (code "34") (name "Net-(D29-A)") (class "Default")
      (node (ref "D29") (pin "1") (pinfunction "A_1") (pintype "passive"))
      (node (ref "D30") (pin "1") (pinfunction "A_1") (pintype "passive"))
      (node (ref "D31") (pin "1") (pinfunction "A_1") (pintype "passive"))
      (node (ref "D32") (pin "1") (pinfunction "A_1") (pintype "passive"))
      (node (ref "Q4") (pin "3") (pinfunction "E_3") (pintype "passive"))
    )
    (net (code "35") (name "Net-(D33-A)") (class "Default")
      (node (ref "D33") (pin "1") (pinfunction "A_1") (pintype "passive"))
      (node (ref "D34") (pin "1") (pinfunction "A_1") (pintype "passive"))
      (node (ref "D35") (pin "1") (pinfunction "A_1") (pintype "passive"))
      (node (ref "D36") (pin "1") (pinfunction "A_1") (pintype "passive"))
      (node (ref "Q5") (pin "3") (pinfunction "E_3") (pintype "passive"))
    )
    (net (code "36") (name "Net-(D37-A)") (class "Default")
      (node (ref "D37") (pin "1") (pinfunction "A_1") (pintype "passive"))
      (node (ref "D38") (pin "1") (pinfunction "A_1") (pintype "passive"))
      (node (ref "D39") (pin "1") (pinfunction "A_1") (pintype "passive"))
      (node (ref "D40") (pin "1") (pinfunction "A_1") (pintype "passive"))
      (node (ref "Q6") (pin "3") (pinfunction "E_3") (pintype "passive"))
    )
    (net (code "37") (name "Net-(D41-A)") (class "Default")
      (node (ref "D41") (pin "1") (pinfunction "A_1") (pintype "passive"))
      (node (ref "D42") (pin "1") (pinfunction "A_1") (pintype "passive"))
      (node (ref "D43") (pin "1") (pinfunction "A_1") (pintype "passive"))
      (node (ref "D44") (pin "1") (pinfunction "A_1") (pintype "passive"))
      (node (ref "Q7") (pin "3") (pinfunction "E_3") (pintype "passive"))
    )
    (net (code "38") (name "Net-(D45-A)") (class "Default")
      (node (ref "D45") (pin "1") (pinfunction "A_1") (pintype "passive"))
      (node (ref "D46") (pin "1") (pinfunction "A_1") (pintype "passive"))
      (node (ref "D47") (pin "1") (pinfunction "A_1") (pintype "passive"))
      (node (ref "D48") (pin "1") (pinfunction "A_1") (pintype "passive"))
      (node (ref "Q8") (pin "3") (pinfunction "E_3") (pintype "passive"))
    )
    (net (code "39") (name "Net-(Q1-B)") (class "Default")
      (node (ref "Q1") (pin "2") (pinfunction "B_2") (pintype "passive"))
      (node (ref "U1") (pin "23") (pinfunction "P2.0_23") (pintype "passive"))
    )
    (net (code "40") (name "Net-(Q2-B)") (class "Default")
      (node (ref "Q2") (pin "2") (pinfunction "B_2") (pintype "passive"))
      (node (ref "U1") (pin "24") (pinfunction "P2.1_24") (pintype "passive"))
    )
    (net (code "41") (name "Net-(Q3-B)") (class "Default")
      (node (ref "Q3") (pin "2") (pinfunction "B_2") (pintype "passive"))
      (node (ref "U1") (pin "25") (pinfunction "P2.2_25") (pintype "passive"))
    )
    (net (code "42") (name "Net-(Q4-B)") (class "Default")
      (node (ref "Q4") (pin "2") (pinfunction "B_2") (pintype "passive"))
      (node (ref "U1") (pin "26") (pinfunction "P2.3_26") (pintype "passive"))
    )
    (net (code "43") (name "Net-(Q5-B)") (class "Default")
      (node (ref "Q5") (pin "2") (pinfunction "B_2") (pintype "passive"))
      (node (ref "U1") (pin "27") (pinfunction "P2.4_27") (pintype "passive"))
    )
    (net (code "44") (name "Net-(Q6-B)") (class "Default")
      (node (ref "Q6") (pin "2") (pinfunction "B_2") (pintype "passive"))
      (node (ref "U1") (pin "28") (pinfunction "P2.5_28") (pintype "passive"))
    )
    (net (code "45") (name "Net-(Q7-B)") (class "Default")
      (node (ref "Q7") (pin "2") (pinfunction "B_2") (pintype "passive"))
      (node (ref "U1") (pin "1") (pinfunction "P2.6_1") (pintype "passive"))
    )
    (net (code "46") (name "Net-(Q8-B)") (class "Default")
      (node (ref "Q8") (pin "2") (pinfunction "B_2") (pintype "passive"))
      (node (ref "U1") (pin "2") (pinfunction "P2.7_2") (pintype "passive"))
    )
    (net (code "47") (name "Net-(U2A-INA+)") (class "Default")
      (node (ref "C1") (pin "1") (pinfunction "1_1") (pintype "passive"))
      (node (ref "R17") (pin "1") (pinfunction "1_1") (pintype "passive"))
      (node (ref "R18") (pin "1") (pinfunction "1_1") (pintype "passive"))
      (node (ref "U2") (pin "3") (pinfunction "INA+_3") (pintype "input"))
      (node (ref "U2") (pin "5") (pinfunction "INB+_5") (pintype "input"))
    )
    (net (code "48") (name "Net-(U2A-INA-)") (class "Default")
      (node (ref "R19") (pin "1") (pinfunction "1_1") (pintype "passive"))
      (node (ref "R20") (pin "2") (pinfunction "2_2") (pintype "passive"))
      (node (ref "U2") (pin "2") (pinfunction "INA-_2") (pintype "input"))
    )
    (net (code "49") (name "Net-(U2A-OUTA)") (class "Default")
      (node (ref "D49") (pin "1") (pinfunction "1_1") (pintype "passive"))
      (node (ref "D49") (pin "2") (pinfunction "2_2") (pintype "passive"))
      (node (ref "D50") (pin "1") (pinfunction "1_1") (pintype "passive"))
      (node (ref "D50") (pin "2") (pinfunction "2_2") (pintype "passive"))
      (node (ref "D51") (pin "1") (pinfunction "1_1") (pintype "passive"))
      (node (ref "D51") (pin "2") (pinfunction "2_2") (pintype "passive"))
      (node (ref "D52") (pin "1") (pinfunction "1_1") (pintype "passive"))
      (node (ref "D52") (pin "2") (pinfunction "2_2") (pintype "passive"))
      (node (ref "R20") (pin "1") (pinfunction "1_1") (pintype "passive"))
      (node (ref "R21") (pin "2") (pinfunction "2_2") (pintype "passive"))
      (node (ref "U2") (pin "1") (pinfunction "OUTA_1") (pintype "output"))
    )
    (net (code "50") (name "Net-(U2B-INB-)") (class "Default")
      (node (ref "R22") (pin "2") (pinfunction "2_2") (pintype "passive"))
      (node (ref "R23") (pin "1") (pinfunction "1_1") (pintype "passive"))
      (node (ref "U2") (pin "6") (pinfunction "INB-_6") (pintype "input"))
    )
    (net (code "51") (name "Net-(U2B-OUTB)") (class "Default")
      (node (ref "D53") (pin "1") (pinfunction "1_1") (pintype "passive"))
      (node (ref "D53") (pin "2") (pinfunction "2_2") (pintype "passive"))
      (node (ref "D54") (pin "1") (pinfunction "1_1") (pintype "passive"))
      (node (ref "D54") (pin "2") (pinfunction "2_2") (pintype "passive"))
      (node (ref "D55") (pin "1") (pinfunction "1_1") (pintype "passive"))
      (node (ref "D55") (pin "2") (pinfunction "2_2") (pintype "passive"))
      (node (ref "D56") (pin "1") (pinfunction "1_1") (pintype "passive"))
      (node (ref "D56") (pin "2") (pinfunction "2_2") (pintype "passive"))
      (node (ref "R23") (pin "2") (pinfunction "2_2") (pintype "passive"))
      (node (ref "R24") (pin "1") (pinfunction "1_1") (pintype "passive"))
      (node (ref "U2") (pin "7") (pinfunction "OUTB_7") (pintype "output"))
    )
    (net (code "52") (name "VCC") (class "Default")
      (node (ref "C4") (pin "1") (pinfunction "1_1") (pintype "passive"))
      (node (ref "C5") (pin "2") (pinfunction "2_2") (pintype "passive"))
      (node (ref "D10") (pin "2") (pinfunction "K_2") (pintype "passive"))
      (node (ref "D11") (pin "2") (pinfunction "K_2") (pintype "passive"))
      (node (ref "D12") (pin "2") (pinfunction "K_2") (pintype "passive"))
      (node (ref "D13") (pin "2") (pinfunction "K_2") (pintype "passive"))
      (node (ref "D14") (pin "2") (pinfunction "K_2") (pintype "passive"))
      (node (ref "D15") (pin "2") (pinfunction "K_2") (pintype "passive"))
      (node (ref "D16") (pin "2") (pinfunction "K_2") (pintype "passive"))
      (node (ref "D9") (pin "2") (pinfunction "K_2") (pintype "passive"))
      (node (ref "P1") (pin "1") (pinfunction "1_1") (pintype "passive"))
      (node (ref "P1") (pin "2") (pinfunction "2_2") (pintype "passive"))
      (node (ref "P1") (pin "3") (pinfunction "3_3") (pintype "passive"))
      (node (ref "P2") (pin "1") (pinfunction "1_1") (pintype "passive"))
      (node (ref "P2") (pin "2") (pinfunction "2_2") (pintype "passive"))
      (node (ref "P2") (pin "3") (pinfunction "3_3") (pintype "passive"))
      (node (ref "P3") (pin "1") (pinfunction "1_1") (pintype "passive"))
      (node (ref "P3") (pin "2") (pinfunction "2_2") (pintype "passive"))
      (node (ref "P3") (pin "3") (pinfunction "3_3") (pintype "passive"))
      (node (ref "P4") (pin "1") (pinfunction "1_1") (pintype "passive"))
      (node (ref "P4") (pin "2") (pinfunction "2_2") (pintype "passive"))
      (node (ref "P4") (pin "3") (pinfunction "3_3") (pintype "passive"))
      (node (ref "P6") (pin "1") (pinfunction "1_1") (pintype "passive"))
      (node (ref "P7") (pin "1") (pinfunction "1_1") (pintype "passive"))
      (node (ref "Q1") (pin "1") (pinfunction "C_1") (pintype "passive"))
      (node (ref "Q2") (pin "1") (pinfunction "C_1") (pintype "passive"))
      (node (ref "Q3") (pin "1") (pinfunction "C_1") (pintype "passive"))
      (node (ref "Q4") (pin "1") (pinfunction "C_1") (pintype "passive"))
      (node (ref "Q5") (pin "1") (pinfunction "C_1") (pintype "passive"))
      (node (ref "Q6") (pin "1") (pinfunction "C_1") (pintype "passive"))
      (node (ref "Q7") (pin "1") (pinfunction "C_1") (pintype "passive"))
      (node (ref "Q8") (pin "1") (pinfunction "C_1") (pintype "passive"))
      (node (ref "R1") (pin "2") (pinfunction "2_2") (pintype "passive"))
      (node (ref "R2") (pin "2") (pinfunction "2_2") (pintype "passive"))
      (node (ref "R25") (pin "2") (pinfunction "2_2") (pintype "passive"))
      (node (ref "R3") (pin "2") (pinfunction "2_2") (pintype "passive"))
      (node (ref "R4") (pin "2") (pinfunction "2_2") (pintype "passive"))
      (node (ref "R5") (pin "2") (pinfunction "2_2") (pintype "passive"))
      (node (ref "R6") (pin "2") (pinfunction "2_2") (pintype "passive"))
      (node (ref "R7") (pin "2") (pinfunction "2_2") (pintype "passive"))
      (node (ref "R8") (pin "2") (pinfunction "2_2") (pintype "passive"))
      (node (ref "U1") (pin "12") (pinfunction "VCC_12") (pintype "passive"))
    )
    (net (code "53") (name "VCC1") (class "Default")
      (node (ref "P1") (pin "4") (pinfunction "4_4") (pintype "passive"))
      (node (ref "P2") (pin "4") (pinfunction "4_4") (pintype "passive"))
      (node (ref "P3") (pin "4") (pinfunction "4_4") (pintype "passive"))
      (node (ref "P4") (pin "4") (pinfunction "4_4") (pintype "passive"))
      (node (ref "P7") (pin "2") (pinfunction "2_2") (pintype "passive"))
      (node (ref "R17") (pin "2") (pinfunction "2_2") (pintype "passive"))
      (node (ref "U2") (pin "8") (pinfunction "V+_8") (pintype "power_in"))
    )
    (net (code "54") (name "unconnected-(U1-P5.4-Pad11)") (class "Default")
      (node (ref "U1") (pin "11") (pinfunction "P5.4_11") (pintype "passive"))
    )
    (net (code "55") (name "unconnected-(U1-P5.5-Pad13)") (class "Default")
      (node (ref "U1") (pin "13") (pinfunction "P5.5_13") (pintype "passive"))
    )
  )
)
